# PWR_LDv6_1.net
KiCad netlist of a schematic drawn in Altium Designer
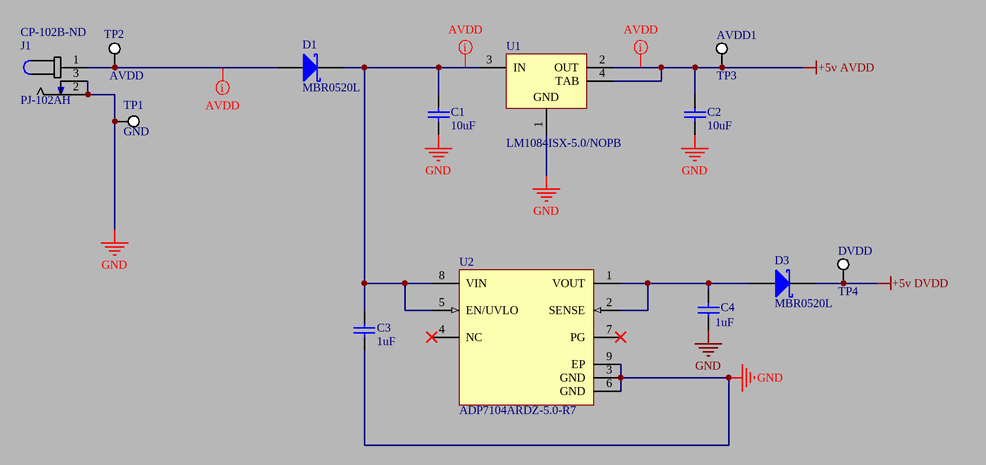
[diagram p0: PWR_LDv6.1.SchDoc]

(export (version "E")
  (design (tool "Eeschema 10.0.6"))
  (components
    (comp (ref "AVDD1")
      (value "TP3")
      (footprint "KSTN-5015_V")
      (description "Test Point, White, SMT")
      (fields (field (name "MANUFACTURER") "Keystone"))
      (libsource (lib "Test Point 2.66mm") (part "CMP-2000-05183-1"))
    )
    (comp (ref "C1")
      (value "10uF")
      (footprint "CAPC1608X90X35ML10T15")
      (fields (field (name "PART NUMBER") "GRM188R60G106ME47J") (field (name "MANUFACTURER") "Murata"))
      (libsource (lib "10uF Cap 0603") (part "CMP-2006-02549-1"))
    )
    (comp (ref "C2")
      (value "10uF")
      (footprint "CAPC1608X90X35ML10T15")
      (fields (field (name "PART NUMBER") "GRM188R60G106ME47J") (field (name "MANUFACTURER") "Murata"))
      (libsource (lib "10uF Cap 0603") (part "CMP-2006-02549-1"))
    )
    (comp (ref "C3")
      (value "1uF")
      (footprint "CAPC1608X90X35ML15T15")
      (fields
        (field (name "PART NUMBER") "06036D105KAT2A")
        (field (name "MANUFACTURER") "AVX Interconnect / Elco")
      )
      (libsource (lib "1uF Cap 0603") (part "CMP-2006-04474-1"))
    )
    (comp (ref "C4")
      (value "1uF")
      (footprint "CAPC1608X90X35ML15T15")
      (fields
        (field (name "PART NUMBER") "06036D105KAT2A")
        (field (name "MANUFACTURER") "AVX Interconnect / Elco")
      )
      (libsource (lib "1uF Cap 0603") (part "CMP-2006-04474-1"))
    )
    (comp (ref "D1")
      (value "MBR0520L")
      (footprint "ONSC-SOD-123-2-425-04_V")
      (description "Schottky Diode, 20V, 0.2A, 2-pin SOD-123, RoHS, Tape and Reel")
      (fields (field (name "MANUFACTURER") "FairchildSemiconductor"))
      (libsource (lib "Diode 20v 500mA 0603") (part "CMP-2000-04926-1"))
    )
    (comp (ref "D3")
      (value "MBR0520L")
      (footprint "ONSC-SOD-123-2-425-04_V")
      (description "Schottky Diode, 20V, 0.2A, 2-pin SOD-123, RoHS, Tape and Reel")
      (fields (field (name "MANUFACTURER") "FairchildSemiconductor"))
      (libsource (lib "Diode 20v 500mA 0603") (part "CMP-2000-04926-1"))
    )
    (comp (ref "DVDD")
      (value "TP4")
      (footprint "KSTN-5015_V")
      (description "Test Point, White, SMT")
      (fields (field (name "MANUFACTURER") "Keystone"))
      (libsource (lib "Test Point 2.66mm") (part "CMP-2000-05183-1"))
    )
    (comp (ref "J1")
      (value "PJ-102AH")
      (footprint "*CUI_PJ-102AH")
      (fields (field (name "SUPPLIER PART NUMBER 1") "CP-102B-ND"))
      (libsource (lib "LDv6") (part "PJ-102AH"))
    )
    (comp (ref "TP1")
      (value "GND")
      (footprint "KSTN-5015_V")
      (description "Test Point, White, SMT")
      (fields (field (name "MANUFACTURER") "Keystone"))
      (libsource (lib "Test Point 2.66mm") (part "CMP-2000-05183-1"))
    )
    (comp (ref "TP2")
      (value "AVDD")
      (footprint "KSTN-5015_V")
      (description "Test Point, White, SMT")
      (fields (field (name "MANUFACTURER") "Keystone"))
      (libsource (lib "Test Point 2.66mm") (part "CMP-2000-05183-1"))
    )
    (comp (ref "U1")
      (value "LM1084ISX-5.0/NOPB")
      (footprint "KTT0003B_M")
      (description "5A Low Dropout Positive Regulators, 3-pin TO-263, Pb-Free")
      (fields (field (name "MANUFACTURER") "Texas Instruments"))
      (libsource (lib "LM1084ISX-5.0_NOPB") (part "CMP-0062-00576-5"))
    )
    (comp (ref "U2")
      (value "ADP7104ARDZ-5.0-R7")
      (footprint "ADI-RD-8-2_N")
      (description "500 mA, Low Noise, CMOS LDO, 3.3 to 20 V Vin, 5 V Vout, Industrial, 8-pin SOIC (RD-8-2), Reel")
      (fields (field (name "MANUFACTURER") "Analog Devices"))
      (libsource (lib "ADP7104 Fixed 5v Reg") (part "CMP-0786-00202-1"))
    )
  )
  (nets
    (net (code "1") (name "+5v AVDD") (class "Default")
      (node (ref "AVDD1") (pin "1") (pinfunction "1_1") (pintype "passive"))
      (node (ref "C2") (pin "2") (pinfunction "2_2") (pintype "passive"))
      (node (ref "U1") (pin "2") (pinfunction "OUT_2") (pintype "power_in"))
      (node (ref "U1") (pin "4") (pinfunction "TAB_4") (pintype "power_in"))
    )
    (net (code "2") (name "+5v DVDD") (class "Default")
      (node (ref "D3") (pin "1") (pinfunction "K_1") (pintype "passive"))
      (node (ref "DVDD") (pin "1") (pinfunction "1_1") (pintype "passive"))
    )
    (net (code "3") (name "GND") (class "Default")
      (node (ref "C1") (pin "1") (pinfunction "1_1") (pintype "passive"))
      (node (ref "C2") (pin "1") (pinfunction "1_1") (pintype "passive"))
      (node (ref "C3") (pin "2") (pinfunction "2_2") (pintype "passive"))
      (node (ref "C4") (pin "1") (pinfunction "1_1") (pintype "passive"))
      (node (ref "J1") (pin "2") (pinfunction "2_2") (pintype "passive"))
      (node (ref "J1") (pin "3") (pinfunction "3_3") (pintype "passive"))
      (node (ref "TP1") (pin "1") (pinfunction "1_1") (pintype "passive"))
      (node (ref "U1") (pin "1") (pinfunction "GND_1") (pintype "power_in"))
      (node (ref "U2") (pin "3") (pinfunction "GND_3") (pintype "power_in"))
      (node (ref "U2") (pin "6") (pinfunction "GND_6") (pintype "power_in"))
      (node (ref "U2") (pin "9") (pinfunction "EP_9") (pintype "power_in"))
    )
    (net (code "4") (name "Net-(D1-A)") (class "Default")
      (node (ref "D1") (pin "2") (pinfunction "A_2") (pintype "passive"))
      (node (ref "J1") (pin "1") (pinfunction "1_1") (pintype "passive"))
      (node (ref "TP2") (pin "1") (pinfunction "1_1") (pintype "passive"))
    )
    (net (code "5") (name "Net-(D1-K)") (class "Default")
      (node (ref "C1") (pin "2") (pinfunction "2_2") (pintype "passive"))
      (node (ref "C3") (pin "1") (pinfunction "1_1") (pintype "passive"))
      (node (ref "D1") (pin "1") (pinfunction "K_1") (pintype "passive"))
      (node (ref "U1") (pin "3") (pinfunction "IN_3") (pintype "power_in"))
      (node (ref "U2") (pin "5") (pinfunction "EN/UVLO_5") (pintype "input"))
      (node (ref "U2") (pin "8") (pinfunction "VIN_8") (pintype "power_in"))
    )
    (net (code "6") (name "Net-(D3-A)") (class "Default")
      (node (ref "C4") (pin "2") (pinfunction "2_2") (pintype "passive"))
      (node (ref "D3") (pin "2") (pinfunction "A_2") (pintype "passive"))
      (node (ref "U2") (pin "1") (pinfunction "VOUT_1") (pintype "power_in"))
      (node (ref "U2") (pin "2") (pinfunction "SENSE_2") (pintype "input"))
    )
    (net (code "7") (name "unconnected-(U2-NC-Pad4)") (class "Default")
      (node (ref "U2") (pin "4") (pinfunction "NC_4") (pintype "passive+no_connect"))
    )
    (net (code "8") (name "unconnected-(U2-PG-Pad7)") (class "Default")
      (node (ref "U2") (pin "7") (pinfunction "PG_7") (pintype "open_collector+no_connect"))
    )
  )
)
